# TB6600.net
KiCad netlist of a schematic drawn in EasyEDA Pro
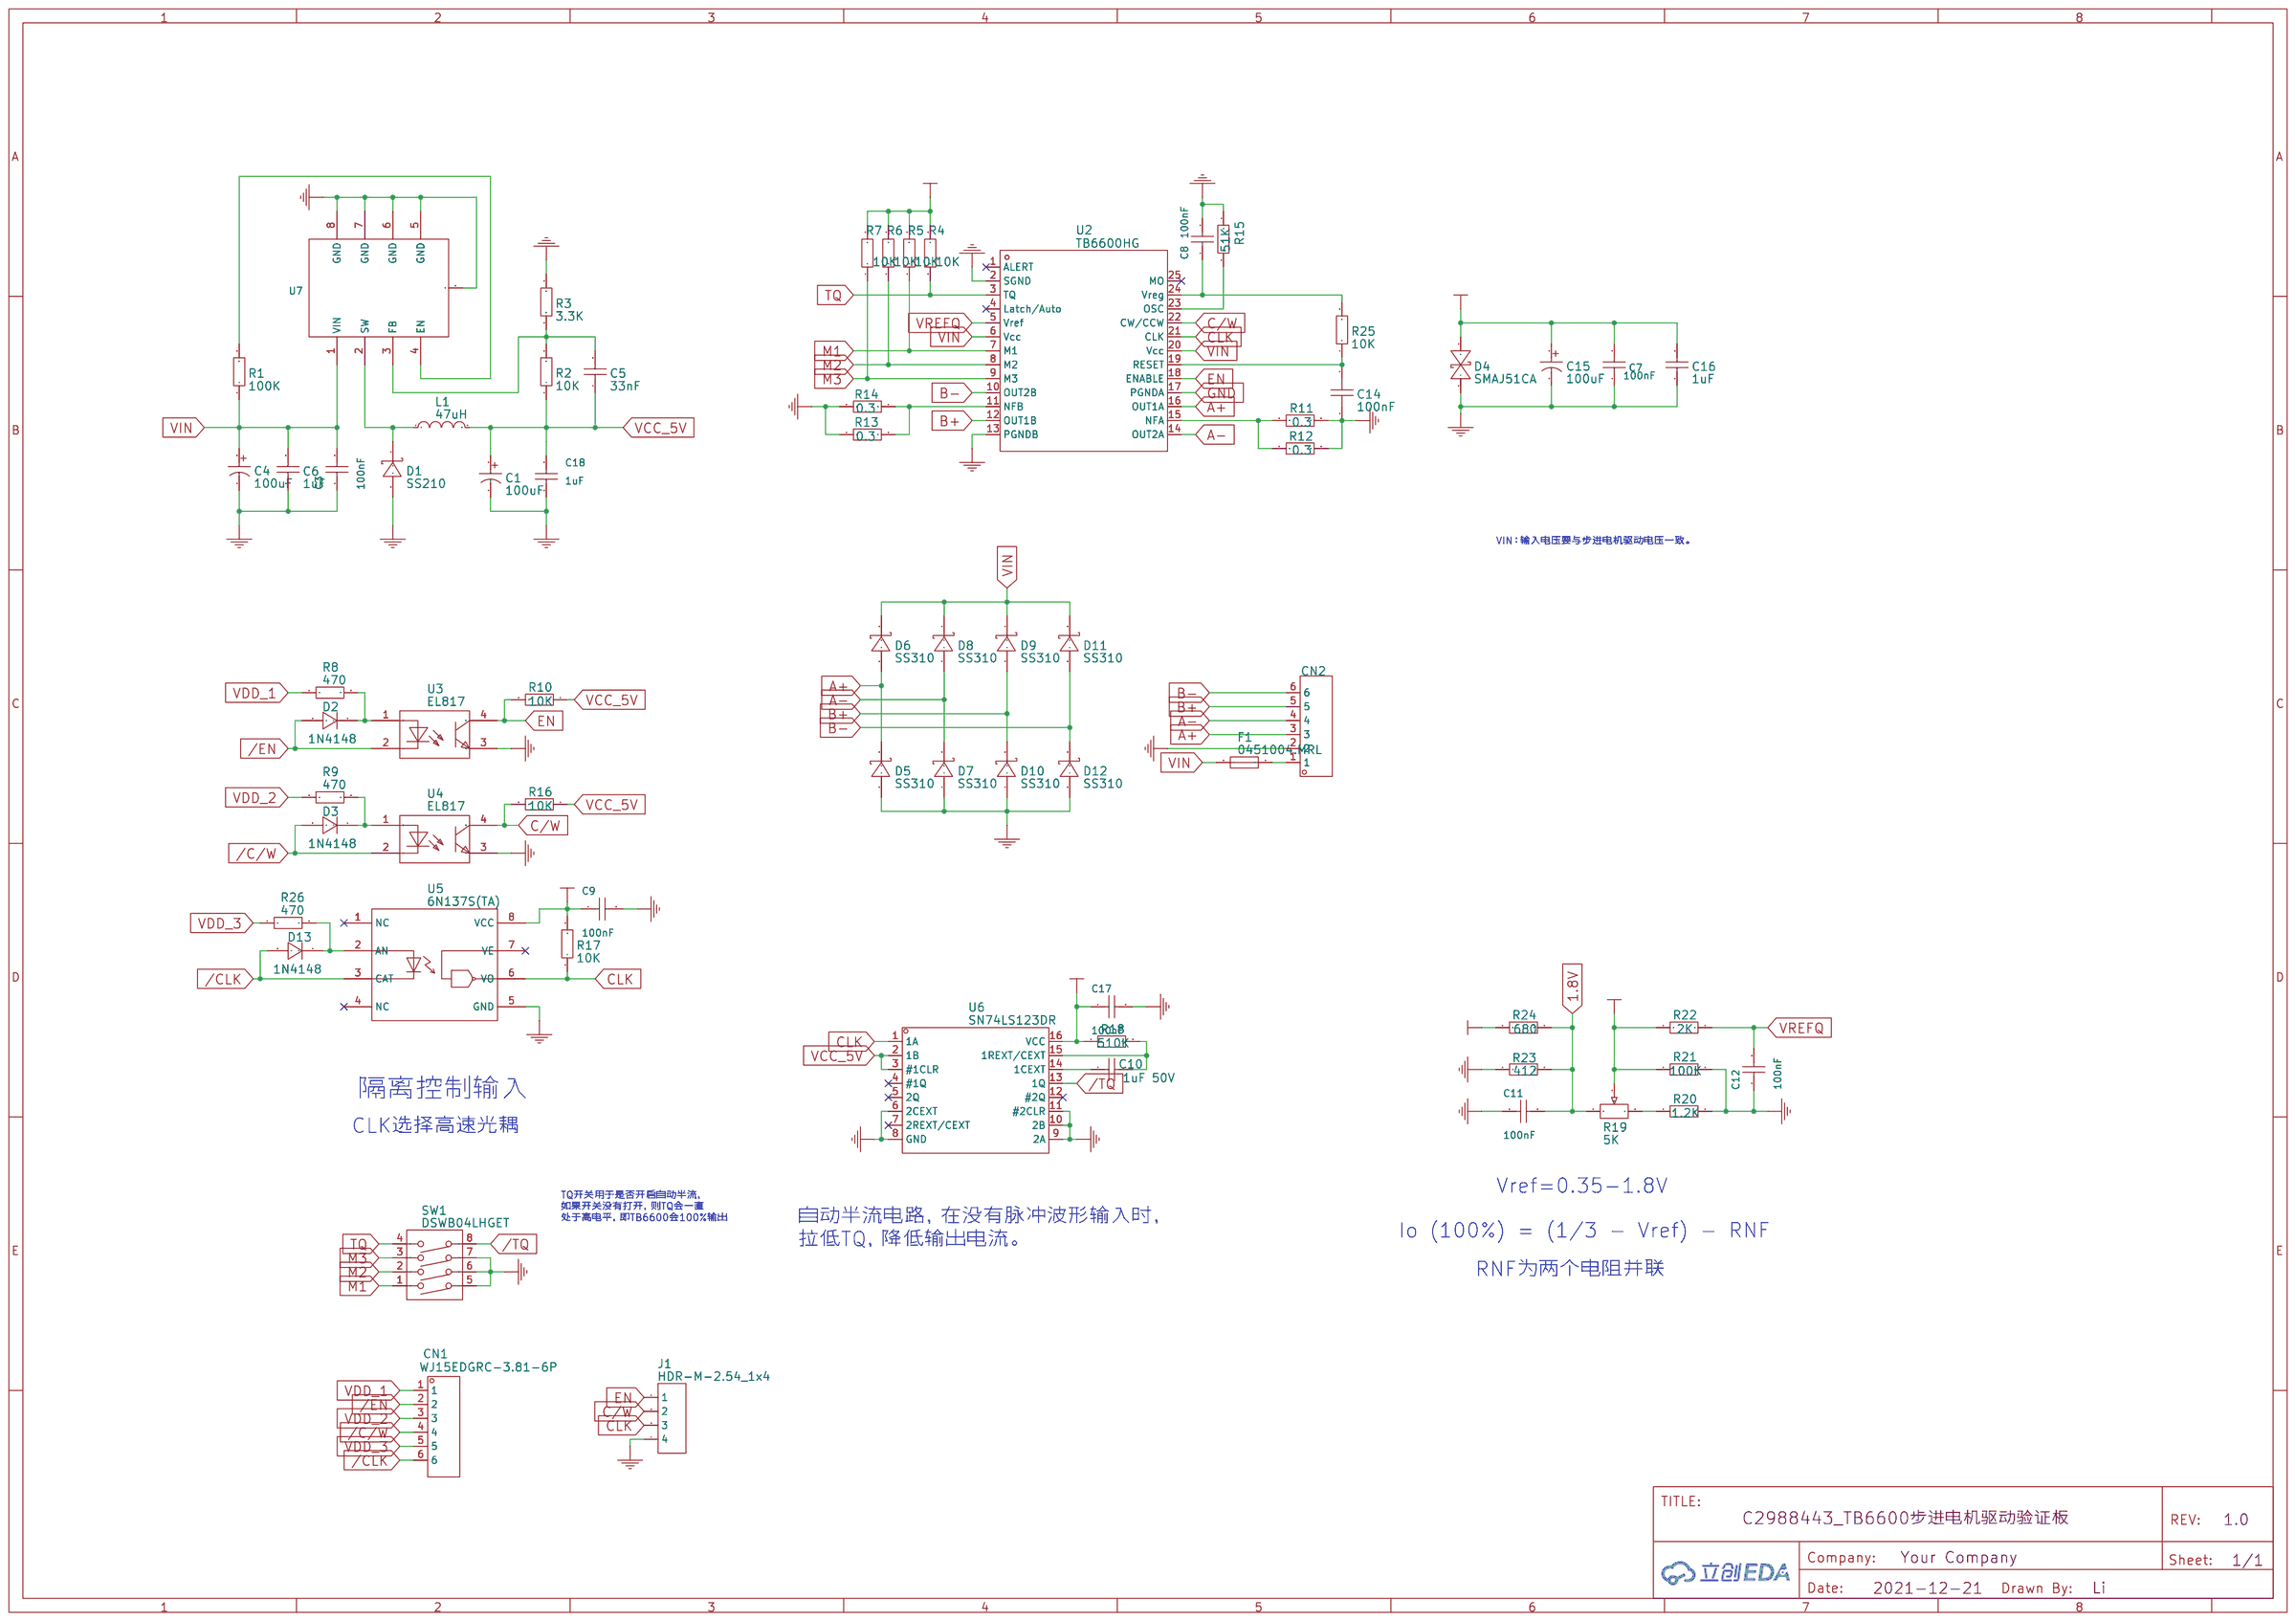
[diagram p0: schematic sheet]

(export (version "E")
  (design (tool "Eeschema 10.0.6"))
  (components
    (comp (ref "C1")
      (value "100uF")
      (footprint "easyedapro:CAP-TH_BD8.0-P3.50-D0.6-FD")
      (fields (field (name "Manufacturer Part") "50V 100uF 8X12") (field (name "Manufacturer") "ValuePro"))
      (libsource (lib "easyedapro") (part "100uF"))
    )
    (comp (ref "C3")
      (value "100nF")
      (footprint "easyedapro:C0603_1")
      (description "容值:100nF;精度:±10%;额定电压:50V;温度系数:X7R;")
      (fields (field (name "Manufacturer Part") "0603B104K500NT") (field (name "Manufacturer") "FH(风华)"))
      (libsource (lib "easyedapro") (part "0603B104K500NT"))
    )
    (comp (ref "C4")
      (value "100uF")
      (footprint "easyedapro:CAP-TH_BD8.0-P3.50-D0.6-FD")
      (fields (field (name "Manufacturer Part") "50V 100uF 8X12") (field (name "Manufacturer") "ValuePro"))
      (libsource (lib "easyedapro") (part "100uF"))
    )
    (comp (ref "C5")
      (value "33nF")
      (footprint "easyedapro:C0603")
      (fields
        (field (name "Manufacturer Part") "CL10B333JB8NNNC")
        (field (name "Manufacturer") "Samsung Electro-Mechanics")
      )
      (libsource (lib "easyedapro") (part "33nF"))
    )
    (comp (ref "C6")
      (value "1uF")
      (footprint "easyedapro:C0805")
      (fields (field (name "Manufacturer Part") "CL21B105KBFNNNE") (field (name "Manufacturer") "SAMSUNG"))
      (libsource (lib "easyedapro") (part "1uF"))
    )
    (comp (ref "C7")
      (value "100nF")
      (footprint "easyedapro:C0603_1")
      (description "容值:100nF;精度:±10%;额定电压:50V;温度系数:X7R;")
      (fields (field (name "Manufacturer Part") "0603B104K500NT") (field (name "Manufacturer") "FH(风华)"))
      (libsource (lib "easyedapro") (part "0603B104K500NT"))
    )
    (comp (ref "C8")
      (value "100nF")
      (footprint "easyedapro:C0603_1")
      (description "容值:100nF;精度:±10%;额定电压:50V;温度系数:X7R;")
      (fields (field (name "Manufacturer Part") "0603B104K500NT") (field (name "Manufacturer") "FH(风华)"))
      (libsource (lib "easyedapro") (part "0603B104K500NT"))
    )
    (comp (ref "C9")
      (value "100nF")
      (footprint "easyedapro:C0603_1")
      (description "容值:100nF;精度:±10%;额定电压:50V;温度系数:X7R;")
      (fields (field (name "Manufacturer Part") "0603B104K500NT") (field (name "Manufacturer") "FH(风华)"))
      (libsource (lib "easyedapro") (part "0603B104K500NT"))
    )
    (comp (ref "C10")
      (value "1uF 50V")
      (footprint "easyedapro:C0603")
      (fields (field (name "Manufacturer Part") "CL10A105KB8NNNC") (field (name "Manufacturer") "SAMSUNG"))
      (libsource (lib "easyedapro") (part "1uF 50V"))
    )
    (comp (ref "C11")
      (value "100nF")
      (footprint "easyedapro:C0603_1")
      (description "容值:100nF;精度:±10%;额定电压:50V;温度系数:X7R;")
      (fields (field (name "Manufacturer Part") "0603B104K500NT") (field (name "Manufacturer") "FH(风华)"))
      (libsource (lib "easyedapro") (part "0603B104K500NT"))
    )
    (comp (ref "C12")
      (value "100nF")
      (footprint "easyedapro:C0603_1")
      (description "容值:100nF;精度:±10%;额定电压:50V;温度系数:X7R;")
      (fields (field (name "Manufacturer Part") "0603B104K500NT") (field (name "Manufacturer") "FH(风华)"))
      (libsource (lib "easyedapro") (part "0603B104K500NT"))
    )
    (comp (ref "C14")
      (value "100nF")
      (footprint "easyedapro:C0603")
      (fields (field (name "Manufacturer Part") "0603B104K500NT") (field (name "Manufacturer") "FH"))
      (libsource (lib "easyedapro") (part "100nF"))
    )
    (comp (ref "C15")
      (value "100uF")
      (footprint "easyedapro:CAP-TH_BD8.0-P3.50-D0.6-FD")
      (fields (field (name "Manufacturer Part") "50V 100uF 8X12") (field (name "Manufacturer") "ValuePro"))
      (libsource (lib "easyedapro") (part "100uF"))
    )
    (comp (ref "C16")
      (value "1uF")
      (footprint "easyedapro:C0805")
      (fields (field (name "Manufacturer Part") "CL21B105KBFNNNE") (field (name "Manufacturer") "SAMSUNG"))
      (libsource (lib "easyedapro") (part "1uF"))
    )
    (comp (ref "C17")
      (value "100nF")
      (footprint "easyedapro:C0603_1")
      (description "容值:100nF;精度:±10%;额定电压:50V;温度系数:X7R;")
      (fields (field (name "Manufacturer Part") "0603B104K500NT") (field (name "Manufacturer") "FH(风华)"))
      (libsource (lib "easyedapro") (part "0603B104K500NT"))
    )
    (comp (ref "C18")
      (value "1uF")
      (footprint "easyedapro:C0603_1")
      (description "容值:1uF;精度:±10%;额定电压:50V;温度系数:X5R;")
      (fields
        (field (name "Manufacturer Part") "CL10A105KB8NNNC")
        (field (name "Manufacturer") "SAMSUNG(三星)")
      )
      (libsource (lib "easyedapro") (part "CL10A105KB8NNNC"))
    )
    (comp (ref "CN1")
      (value "WJ15EDGRC-3.81-6P")
      (footprint "easyedapro:CONN-TH_WJ15EDGRC-3.81-6P")
      (fields (field (name "Manufacturer") "ReliaPro"))
      (libsource (lib "easyedapro") (part "WJ15EDGRC-3.81-6P"))
    )
    (comp (ref "CN2")
      (value "WJ15EDGRC-3.81-6P")
      (footprint "easyedapro:CONN-TH_WJ15EDGRC-3.81-6P")
      (fields (field (name "Manufacturer") "ReliaPro"))
      (libsource (lib "easyedapro") (part "WJ15EDGRC-3.81-6P"))
    )
    (comp (ref "D1")
      (value "SS210")
      (footprint "easyedapro:SMA_L4.3-W2.6-LS5.2-RD")
      (fields (field (name "Manufacturer") "MDD"))
      (libsource (lib "easyedapro") (part "SS210"))
    )
    (comp (ref "D2")
      (value "1N4148")
      (footprint "easyedapro:SOD-123_L2.8-W1.8-LS3.7-RD")
      (fields (field (name "Manufacturer Part") "1N4148W T4") (field (name "Manufacturer") "CJ"))
      (libsource (lib "easyedapro") (part "1N4148"))
    )
    (comp (ref "D3")
      (value "1N4148")
      (footprint "easyedapro:SOD-123_L2.8-W1.8-LS3.7-RD")
      (fields (field (name "Manufacturer Part") "1N4148W T4") (field (name "Manufacturer") "CJ"))
      (libsource (lib "easyedapro") (part "1N4148"))
    )
    (comp (ref "D4")
      (value "SMAJ51CA")
      (footprint "easyedapro:SMA_L4.4-W2.6-LS5.0-BI")
      (fields (field (name "Manufacturer") "MDD（Microdiode Electronics）"))
      (libsource (lib "easyedapro") (part "SMAJ51CA"))
    )
    (comp (ref "D5")
      (value "SS310")
      (footprint "easyedapro:SMA_L4.3-W2.6-LS5.2-RD")
      (fields (field (name "Manufacturer") "MDD"))
      (libsource (lib "easyedapro") (part "SS310"))
    )
    (comp (ref "D6")
      (value "SS310")
      (footprint "easyedapro:SMA_L4.3-W2.6-LS5.2-RD")
      (fields (field (name "Manufacturer") "MDD"))
      (libsource (lib "easyedapro") (part "SS310"))
    )
    (comp (ref "D7")
      (value "SS310")
      (footprint "easyedapro:SMA_L4.3-W2.6-LS5.2-RD")
      (fields (field (name "Manufacturer") "MDD"))
      (libsource (lib "easyedapro") (part "SS310"))
    )
    (comp (ref "D8")
      (value "SS310")
      (footprint "easyedapro:SMA_L4.3-W2.6-LS5.2-RD")
      (fields (field (name "Manufacturer") "MDD"))
      (libsource (lib "easyedapro") (part "SS310"))
    )
    (comp (ref "D9")
      (value "SS310")
      (footprint "easyedapro:SMA_L4.3-W2.6-LS5.2-RD")
      (fields (field (name "Manufacturer") "MDD"))
      (libsource (lib "easyedapro") (part "SS310"))
    )
    (comp (ref "D10")
      (value "SS310")
      (footprint "easyedapro:SMA_L4.3-W2.6-LS5.2-RD")
      (fields (field (name "Manufacturer") "MDD"))
      (libsource (lib "easyedapro") (part "SS310"))
    )
    (comp (ref "D11")
      (value "SS310")
      (footprint "easyedapro:SMA_L4.3-W2.6-LS5.2-RD")
      (fields (field (name "Manufacturer") "MDD"))
      (libsource (lib "easyedapro") (part "SS310"))
    )
    (comp (ref "D12")
      (value "SS310")
      (footprint "easyedapro:SMA_L4.3-W2.6-LS5.2-RD")
      (fields (field (name "Manufacturer") "MDD"))
      (libsource (lib "easyedapro") (part "SS310"))
    )
    (comp (ref "D13")
      (value "1N4148")
      (footprint "easyedapro:SOD-123_L2.8-W1.8-LS3.7-RD")
      (fields (field (name "Manufacturer Part") "1N4148W T4") (field (name "Manufacturer") "CJ"))
      (libsource (lib "easyedapro") (part "1N4148"))
    )
    (comp (ref "F1")
      (value "0451004.MRL")
      (footprint "easyedapro:FUSE-SMD_L6.1-W2.7")
      (fields (field (name "Manufacturer") "Littelfuse"))
      (libsource (lib "easyedapro") (part "0451004.MRL"))
    )
    (comp (ref "J1")
      (value "HDR-M-2.54_1x4")
      (footprint "easyedapro:HDR-M-2.54_1X4")
      (libsource (lib "easyedapro") (part "HDR-M-2.54_1x4"))
    )
    (comp (ref "L1")
      (value "47uH")
      (footprint "easyedapro:IND-SMD_L4.0-W4.0_SMNR4018")
      (fields (field (name "Manufacturer Part") "SMNR4018-470MT") (field (name "Manufacturer") "SXN"))
      (libsource (lib "easyedapro") (part "47uH"))
    )
    (comp (ref "R1")
      (value "100K")
      (footprint "easyedapro:R0603")
      (fields (field (name "Manufacturer Part") "0603WAF1003T5E") (field (name "Manufacturer") "UniOhm"))
      (libsource (lib "easyedapro") (part "100K"))
    )
    (comp (ref "R2")
      (value "10K")
      (footprint "easyedapro:R0603")
      (fields (field (name "Manufacturer Part") "RC0603JR-0710KL") (field (name "Manufacturer") "YAGEO"))
      (libsource (lib "easyedapro") (part "10K"))
    )
    (comp (ref "R3")
      (value "3.3K")
      (footprint "easyedapro:R0603")
      (fields (field (name "Manufacturer Part") "0603WAF3301T5E") (field (name "Manufacturer") "UniOhm"))
      (libsource (lib "easyedapro") (part "3.3K"))
    )
    (comp (ref "R4")
      (value "10K")
      (footprint "easyedapro:R0603")
      (fields (field (name "Manufacturer Part") "RC0603JR-0710KL") (field (name "Manufacturer") "YAGEO"))
      (libsource (lib "easyedapro") (part "10K"))
    )
    (comp (ref "R5")
      (value "10K")
      (footprint "easyedapro:R0603")
      (fields (field (name "Manufacturer Part") "RC0603JR-0710KL") (field (name "Manufacturer") "YAGEO"))
      (libsource (lib "easyedapro") (part "10K"))
    )
    (comp (ref "R6")
      (value "10K")
      (footprint "easyedapro:R0603")
      (fields (field (name "Manufacturer Part") "RC0603JR-0710KL") (field (name "Manufacturer") "YAGEO"))
      (libsource (lib "easyedapro") (part "10K"))
    )
    (comp (ref "R7")
      (value "10K")
      (footprint "easyedapro:R0603")
      (fields (field (name "Manufacturer Part") "RC0603JR-0710KL") (field (name "Manufacturer") "YAGEO"))
      (libsource (lib "easyedapro") (part "10K"))
    )
    (comp (ref "R8")
      (value "470")
      (footprint "easyedapro:R0603")
      (fields (field (name "Manufacturer Part") "0603WAF4700T5E") (field (name "Manufacturer") "UniOhm"))
      (libsource (lib "easyedapro") (part "470"))
    )
    (comp (ref "R9")
      (value "470")
      (footprint "easyedapro:R0603")
      (fields (field (name "Manufacturer Part") "0603WAF4700T5E") (field (name "Manufacturer") "UniOhm"))
      (libsource (lib "easyedapro") (part "470"))
    )
    (comp (ref "R10")
      (value "10K")
      (footprint "easyedapro:R0603")
      (fields (field (name "Manufacturer Part") "RC0603JR-0710KL") (field (name "Manufacturer") "YAGEO"))
      (libsource (lib "easyedapro") (part "10K"))
    )
    (comp (ref "R11")
      (value "0.3")
      (footprint "easyedapro:R2512")
      (fields (field (name "Manufacturer Part") "25121WF300LT4F") (field (name "Manufacturer") "UniOhm"))
      (libsource (lib "easyedapro") (part "0.3"))
    )
    (comp (ref "R12")
      (value "0.3")
      (footprint "easyedapro:R2512")
      (fields (field (name "Manufacturer Part") "25121WF300LT4F") (field (name "Manufacturer") "UniOhm"))
      (libsource (lib "easyedapro") (part "0.3"))
    )
    (comp (ref "R13")
      (value "0.3")
      (footprint "easyedapro:R2512")
      (fields (field (name "Manufacturer Part") "25121WF300LT4F") (field (name "Manufacturer") "UniOhm"))
      (libsource (lib "easyedapro") (part "0.3"))
    )
    (comp (ref "R14")
      (value "0.3")
      (footprint "easyedapro:R2512")
      (fields (field (name "Manufacturer Part") "25121WF300LT4F") (field (name "Manufacturer") "UniOhm"))
      (libsource (lib "easyedapro") (part "0.3"))
    )
    (comp (ref "R15")
      (value "51K")
      (footprint "easyedapro:R0603")
      (fields (field (name "Manufacturer Part") "0603WAJ0513T5E") (field (name "Manufacturer") "UniOhm"))
      (libsource (lib "easyedapro") (part "51K"))
    )
    (comp (ref "R16")
      (value "10K")
      (footprint "easyedapro:R0603")
      (fields (field (name "Manufacturer Part") "RC0603JR-0710KL") (field (name "Manufacturer") "YAGEO"))
      (libsource (lib "easyedapro") (part "10K"))
    )
    (comp (ref "R17")
      (value "10K")
      (footprint "easyedapro:R0603")
      (fields (field (name "Manufacturer Part") "RC0603JR-0710KL") (field (name "Manufacturer") "YAGEO"))
      (libsource (lib "easyedapro") (part "10K"))
    )
    (comp (ref "R18")
      (value "510K")
      (footprint "easyedapro:R0603")
      (fields (field (name "Manufacturer Part") "0603WAF5103T5E") (field (name "Manufacturer") "UniOhm"))
      (libsource (lib "easyedapro") (part "510K"))
    )
    (comp (ref "R19")
      (value "5K")
      (footprint "easyedapro:RES-ADJ-TH_3P-L9.5-W9.5-P2.50-L_3386P")
      (fields
        (field (name "Manufacturer Part") "3386P-1-502")
        (field (name "Manufacturer") "Chengdu Guosheng Tech")
      )
      (libsource (lib "easyedapro") (part "5K"))
    )
    (comp (ref "R20")
      (value "1.2K")
      (footprint "easyedapro:R0603")
      (fields (field (name "Manufacturer Part") "0603WAF1201T5E") (field (name "Manufacturer") "UniOhm"))
      (libsource (lib "easyedapro") (part "1.2K"))
    )
    (comp (ref "R21")
      (value "100K")
      (footprint "easyedapro:R0603")
      (fields (field (name "Manufacturer Part") "0603WAF1003T5E") (field (name "Manufacturer") "UniOhm"))
      (libsource (lib "easyedapro") (part "100K"))
    )
    (comp (ref "R22")
      (value "2K")
      (footprint "easyedapro:R0603")
      (fields (field (name "Manufacturer Part") "0603WAF2001T5E") (field (name "Manufacturer") "UniOhm"))
      (libsource (lib "easyedapro") (part "2K"))
    )
    (comp (ref "R23")
      (value "412")
      (footprint "easyedapro:R0603")
      (fields (field (name "Manufacturer Part") "0603WAF4120T5E") (field (name "Manufacturer") "UniOhm"))
      (libsource (lib "easyedapro") (part "412"))
    )
    (comp (ref "R24")
      (value "680")
      (footprint "easyedapro:R0603")
      (fields (field (name "Manufacturer Part") "0603WAF6800T5E") (field (name "Manufacturer") "UniOhm"))
      (libsource (lib "easyedapro") (part "680"))
    )
    (comp (ref "R25")
      (value "10K")
      (footprint "easyedapro:R0603")
      (fields (field (name "Manufacturer Part") "RC0603JR-0710KL") (field (name "Manufacturer") "YAGEO"))
      (libsource (lib "easyedapro") (part "10K"))
    )
    (comp (ref "R26")
      (value "470")
      (footprint "easyedapro:R0603")
      (fields (field (name "Manufacturer Part") "0603WAF4700T5E") (field (name "Manufacturer") "UniOhm"))
      (libsource (lib "easyedapro") (part "470"))
    )
    (comp (ref "SW1")
      (value "DSWB04LHGET")
      (footprint "easyedapro:SW-TH_DSWB04LHGET")
      (fields (field (name "Manufacturer") "Dongguan Guangzhu Industrial"))
      (libsource (lib "easyedapro") (part "DSWB04LHGET"))
    )
    (comp (ref "U2")
      (value "TB6600HG")
      (footprint "easyedapro:HZIP25-P-1.0_TB6600HG")
      (fields (field (name "Manufacturer") "TOSHIBA"))
      (libsource (lib "easyedapro") (part "TB6600HG"))
    )
    (comp (ref "U3")
      (value "EL817")
      (footprint "easyedapro:OPTO-SMD-4_L4.6-W6.5-P2.54-LS10.3-TL")
      (fields (field (name "Manufacturer Part") "EL817S1(C)(TU)-F") (field (name "Manufacturer") "EVERLIGHT"))
      (libsource (lib "easyedapro") (part "EL817"))
    )
    (comp (ref "U4")
      (value "EL817")
      (footprint "easyedapro:OPTO-SMD-4_L4.6-W6.5-P2.54-LS10.3-TL")
      (fields (field (name "Manufacturer Part") "EL817S1(C)(TU)-F") (field (name "Manufacturer") "EVERLIGHT"))
      (libsource (lib "easyedapro") (part "EL817"))
    )
    (comp (ref "U5")
      (value "6N137S(TA)")
      (footprint "easyedapro:SMD-8_L9.8-W6.6-P2.54-LS10.3-BL")
      (fields (field (name "Manufacturer") "EVERLIGHT"))
      (libsource (lib "easyedapro") (part "6N137S(TA)"))
    )
    (comp (ref "U6")
      (value "SN74LS123DR")
      (footprint "easyedapro:SOIC-16_L9.9-W3.9-P1.27-LS6.0-BL")
      (fields (field (name "Manufacturer") "Texas Instruments"))
      (libsource (lib "easyedapro") (part "SN74LS123DR"))
    )
    (comp (ref "U7")
      (value "~")
      (footprint "easyedapro:SOIC-8_L5.0-W4.0-P1.27-LS6.0-BL-EP2.0_1")
      (description "功能类型:降压型;同步整流:-;输出通道数:-;拓扑结构:-;输入电压:-;输出电流(最大值):-;开关频率:-;")
      (fields (field (name "Manufacturer Part") "XL7005A") (field (name "Manufacturer") "XLSEMI(芯龙)"))
      (libsource (lib "easyedapro") (part "XL7005A_1"))
    )
  )
  (nets
    (net (code "1") (name "1.8V") (class "Default")
      (node (ref "C11") (pin "2") (pinfunction "2_2") (pintype "input"))
      (node (ref "R19") (pin "1") (pinfunction "1_1") (pintype "input"))
      (node (ref "R23") (pin "1") (pinfunction "1_1") (pintype "input"))
      (node (ref "R24") (pin "1") (pinfunction "1_1") (pintype "input"))
    )
    (net (code "2") (name "A+") (class "Default")
      (node (ref "CN2") (pin "3") (pinfunction "3_3") (pintype "input"))
      (node (ref "D5") (pin "1") (pinfunction "K_1") (pintype "input"))
      (node (ref "D6") (pin "2") (pinfunction "A_2") (pintype "input"))
      (node (ref "U2") (pin "16") (pinfunction "OUT1A_16") (pintype "input"))
    )
    (net (code "3") (name "A-") (class "Default")
      (node (ref "CN2") (pin "4") (pinfunction "4_4") (pintype "input"))
      (node (ref "D7") (pin "1") (pinfunction "K_1") (pintype "input"))
      (node (ref "D8") (pin "2") (pinfunction "A_2") (pintype "input"))
      (node (ref "U2") (pin "14") (pinfunction "OUT2A_14") (pintype "input"))
    )
    (net (code "4") (name "B+") (class "Default")
      (node (ref "CN2") (pin "5") (pinfunction "5_5") (pintype "input"))
      (node (ref "D10") (pin "1") (pinfunction "K_1") (pintype "input"))
      (node (ref "D9") (pin "2") (pinfunction "A_2") (pintype "input"))
      (node (ref "U2") (pin "12") (pinfunction "OUT1B_12") (pintype "input"))
    )
    (net (code "5") (name "B-") (class "Default")
      (node (ref "CN2") (pin "6") (pinfunction "6_6") (pintype "input"))
      (node (ref "D11") (pin "2") (pinfunction "A_2") (pintype "input"))
      (node (ref "D12") (pin "1") (pinfunction "K_1") (pintype "input"))
      (node (ref "U2") (pin "10") (pinfunction "OUT2B_10") (pintype "input"))
    )
    (net (code "6") (name "CLK") (class "Default")
      (node (ref "J1") (pin "3") (pinfunction "3_3") (pintype "input"))
      (node (ref "R17") (pin "1") (pinfunction "1_1") (pintype "input"))
      (node (ref "U2") (pin "21") (pinfunction "CLK_21") (pintype "input"))
      (node (ref "U5") (pin "6") (pinfunction "VO_6") (pintype "input"))
      (node (ref "U6") (pin "1") (pinfunction "1A_1") (pintype "input"))
    )
    (net (code "7") (name "C{slash}W") (class "Default")
      (node (ref "J1") (pin "2") (pinfunction "2_2") (pintype "input"))
      (node (ref "R16") (pin "2") (pinfunction "2_2") (pintype "input"))
      (node (ref "U2") (pin "22") (pinfunction "CW/CCW_22") (pintype "input"))
      (node (ref "U4") (pin "4") (pinfunction "COL_4") (pintype "input"))
    )
    (net (code "8") (name "EN") (class "Default")
      (node (ref "J1") (pin "1") (pinfunction "1_1") (pintype "input"))
      (node (ref "R10") (pin "2") (pinfunction "2_2") (pintype "input"))
      (node (ref "U2") (pin "18") (pinfunction "ENABLE_18") (pintype "input"))
      (node (ref "U3") (pin "4") (pinfunction "COL_4") (pintype "input"))
    )
    (net (code "9") (name "GND") (class "Default")
      (node (ref "C1") (pin "2") (pinfunction "2_2") (pintype "input"))
      (node (ref "C11") (pin "1") (pinfunction "1_1") (pintype "input"))
      (node (ref "C12") (pin "1") (pinfunction "1_1") (pintype "input"))
      (node (ref "C14") (pin "1") (pinfunction "1_1") (pintype "input"))
      (node (ref "C15") (pin "2") (pinfunction "2_2") (pintype "input"))
      (node (ref "C16") (pin "1") (pinfunction "1_1") (pintype "input"))
      (node (ref "C17") (pin "2") (pinfunction "2_2") (pintype "input"))
      (node (ref "C18") (pin "1") (pinfunction "1_1") (pintype "input"))
      (node (ref "C3") (pin "1") (pinfunction "1_1") (pintype "input"))
      (node (ref "C4") (pin "2") (pinfunction "2_2") (pintype "input"))
      (node (ref "C6") (pin "1") (pinfunction "1_1") (pintype "input"))
      (node (ref "C7") (pin "1") (pinfunction "1_1") (pintype "input"))
      (node (ref "C8") (pin "2") (pinfunction "2_2") (pintype "input"))
      (node (ref "C9") (pin "2") (pinfunction "2_2") (pintype "input"))
      (node (ref "CN2") (pin "2") (pinfunction "2_2") (pintype "input"))
      (node (ref "D1") (pin "2") (pinfunction "A_2") (pintype "input"))
      (node (ref "D10") (pin "2") (pinfunction "A_2") (pintype "input"))
      (node (ref "D12") (pin "2") (pinfunction "A_2") (pintype "input"))
      (node (ref "D4") (pin "1") (pinfunction "A_1") (pintype "input"))
      (node (ref "D5") (pin "2") (pinfunction "A_2") (pintype "input"))
      (node (ref "D7") (pin "2") (pinfunction "A_2") (pintype "input"))
      (node (ref "J1") (pin "4") (pinfunction "4_4") (pintype "input"))
      (node (ref "R11") (pin "2") (pinfunction "2_2") (pintype "input"))
      (node (ref "R12") (pin "2") (pinfunction "2_2") (pintype "input"))
      (node (ref "R13") (pin "1") (pinfunction "1_1") (pintype "input"))
      (node (ref "R14") (pin "1") (pinfunction "1_1") (pintype "input"))
      (node (ref "R15") (pin "2") (pinfunction "2_2") (pintype "input"))
      (node (ref "R20") (pin "2") (pinfunction "2_2") (pintype "input"))
      (node (ref "R21") (pin "2") (pinfunction "2_2") (pintype "input"))
      (node (ref "R23") (pin "2") (pinfunction "2_2") (pintype "input"))
      (node (ref "R3") (pin "2") (pinfunction "2_2") (pintype "input"))
      (node (ref "SW1") (pin "5") (pinfunction "5_5") (pintype "input"))
      (node (ref "SW1") (pin "6") (pinfunction "6_6") (pintype "input"))
      (node (ref "SW1") (pin "7") (pinfunction "7_7") (pintype "input"))
      (node (ref "U2") (pin "13") (pinfunction "PGNDB_13") (pintype "input"))
      (node (ref "U2") (pin "17") (pinfunction "PGNDA_17") (pintype "input"))
      (node (ref "U2") (pin "2") (pinfunction "SGND_2") (pintype "input"))
      (node (ref "U3") (pin "3") (pinfunction "EM_3") (pintype "input"))
      (node (ref "U4") (pin "3") (pinfunction "EM_3") (pintype "input"))
      (node (ref "U5") (pin "5") (pinfunction "GND_5") (pintype "input"))
      (node (ref "U6") (pin "10") (pinfunction "2B_10") (pintype "input"))
      (node (ref "U6") (pin "11") (pinfunction "#2CLR_11") (pintype "input"))
      (node (ref "U6") (pin "6") (pinfunction "2CEXT_6") (pintype "input"))
      (node (ref "U6") (pin "8") (pinfunction "GND_8") (pintype "input"))
      (node (ref "U6") (pin "9") (pinfunction "2A_9") (pintype "input"))
      (node (ref "U7") (pin "5") (pinfunction "GND_5") (pintype "input"))
      (node (ref "U7") (pin "6") (pinfunction "GND_6") (pintype "input"))
      (node (ref "U7") (pin "7") (pinfunction "GND_7") (pintype "input"))
      (node (ref "U7") (pin "8") (pinfunction "GND_8") (pintype "input"))
      (node (ref "U7") (pin "9") (pinfunction "9_9") (pintype "input"))
    )
    (net (code "10") (name "M1") (class "Default")
      (node (ref "R5") (pin "1") (pinfunction "1_1") (pintype "input"))
      (node (ref "SW1") (pin "1") (pinfunction "1_1") (pintype "input"))
      (node (ref "U2") (pin "7") (pinfunction "M1_7") (pintype "input"))
    )
    (net (code "11") (name "M2") (class "Default")
      (node (ref "R6") (pin "1") (pinfunction "1_1") (pintype "input"))
      (node (ref "SW1") (pin "2") (pinfunction "2_2") (pintype "input"))
      (node (ref "U2") (pin "8") (pinfunction "M2_8") (pintype "input"))
    )
    (net (code "12") (name "M3") (class "Default")
      (node (ref "R7") (pin "1") (pinfunction "1_1") (pintype "input"))
      (node (ref "SW1") (pin "3") (pinfunction "3_3") (pintype "input"))
      (node (ref "U2") (pin "9") (pinfunction "M3_9") (pintype "input"))
    )
    (net (code "13") (name "Net-(CN2-Pad1)") (class "Default")
      (node (ref "CN2") (pin "1") (pinfunction "1_1") (pintype "input"))
      (node (ref "F1") (pin "2") (pinfunction "2_2") (pintype "input"))
    )
    (net (code "14") (name "Net-(D1-K)") (class "Default")
      (node (ref "D1") (pin "1") (pinfunction "K_1") (pintype "input"))
      (node (ref "L1") (pin "1") (pinfunction "1_1") (pintype "input"))
      (node (ref "U7") (pin "2") (pinfunction "SW_2") (pintype "input"))
    )
    (net (code "15") (name "Net-(D2-K)") (class "Default")
      (node (ref "D2") (pin "1") (pinfunction "K_1") (pintype "input"))
      (node (ref "R8") (pin "2") (pinfunction "2_2") (pintype "input"))
      (node (ref "U3") (pin "1") (pinfunction "AN_1") (pintype "input"))
    )
    (net (code "16") (name "Net-(D3-K)") (class "Default")
      (node (ref "D3") (pin "1") (pinfunction "K_1") (pintype "input"))
      (node (ref "R9") (pin "2") (pinfunction "2_2") (pintype "input"))
      (node (ref "U4") (pin "1") (pinfunction "AN_1") (pintype "input"))
    )
    (net (code "17") (name "Net-(D13-K)") (class "Default")
      (node (ref "D13") (pin "1") (pinfunction "K_1") (pintype "input"))
      (node (ref "R26") (pin "2") (pinfunction "2_2") (pintype "input"))
      (node (ref "U5") (pin "2") (pinfunction "AN_2") (pintype "input"))
    )
    (net (code "18") (name "Net-(R19-Pad3)") (class "Default")
      (node (ref "R19") (pin "3") (pinfunction "3_3") (pintype "input"))
      (node (ref "R20") (pin "1") (pinfunction "1_1") (pintype "input"))
    )
    (net (code "19") (name "Net-(U2-NFA)") (class "Default")
      (node (ref "R11") (pin "1") (pinfunction "1_1") (pintype "input"))
      (node (ref "R12") (pin "1") (pinfunction "1_1") (pintype "input"))
      (node (ref "U2") (pin "15") (pinfunction "NFA_15") (pintype "input"))
    )
    (net (code "20") (name "Net-(U2-NFB)") (class "Default")
      (node (ref "R13") (pin "2") (pinfunction "2_2") (pintype "input"))
      (node (ref "R14") (pin "2") (pinfunction "2_2") (pintype "input"))
      (node (ref "U2") (pin "11") (pinfunction "NFB_11") (pintype "input"))
    )
    (net (code "21") (name "Net-(U2-OSC)") (class "Default")
      (node (ref "R15") (pin "1") (pinfunction "1_1") (pintype "input"))
      (node (ref "U2") (pin "23") (pinfunction "OSC_23") (pintype "input"))
    )
    (net (code "22") (name "Net-(U2-RESET)") (class "Default")
      (node (ref "C14") (pin "2") (pinfunction "2_2") (pintype "input"))
      (node (ref "R25") (pin "1") (pinfunction "1_1") (pintype "input"))
      (node (ref "U2") (pin "19") (pinfunction "RESET_19") (pintype "input"))
    )
    (net (code "23") (name "Net-(U2-Vreg)") (class "Default")
      (node (ref "C8") (pin "1") (pinfunction "1_1") (pintype "input"))
      (node (ref "R25") (pin "2") (pinfunction "2_2") (pintype "input"))
      (node (ref "U2") (pin "24") (pinfunction "Vreg_24") (pintype "input"))
    )
    (net (code "24") (name "Net-(U6-1CEXT)") (class "Default")
      (node (ref "C10") (pin "2") (pinfunction "2_2") (pintype "input"))
      (node (ref "U6") (pin "14") (pinfunction "1CEXT_14") (pintype "input"))
    )
    (net (code "25") (name "Net-(U6-1REXT{slash}CEXT)") (class "Default")
      (node (ref "C10") (pin "1") (pinfunction "1_1") (pintype "input"))
      (node (ref "R18") (pin "2") (pinfunction "2_2") (pintype "input"))
      (node (ref "U6") (pin "15") (pinfunction "1REXT/CEXT_15") (pintype "input"))
    )
    (net (code "26") (name "Net-(U7-EN)") (class "Default")
      (node (ref "R1") (pin "2") (pinfunction "2_2") (pintype "input"))
      (node (ref "U7") (pin "4") (pinfunction "EN_4") (pintype "input"))
    )
    (net (code "27") (name "Net-(U7-FB)") (class "Default")
      (node (ref "C5") (pin "2") (pinfunction "2_2") (pintype "input"))
      (node (ref "R2") (pin "2") (pinfunction "2_2") (pintype "input"))
      (node (ref "R3") (pin "1") (pinfunction "1_1") (pintype "input"))
      (node (ref "U7") (pin "3") (pinfunction "FB_3") (pintype "input"))
    )
    (net (code "28") (name "TQ") (class "Default")
      (node (ref "R4") (pin "1") (pinfunction "1_1") (pintype "input"))
      (node (ref "SW1") (pin "4") (pinfunction "4_4") (pintype "input"))
      (node (ref "U2") (pin "3") (pinfunction "TQ_3") (pintype "input"))
    )
    (net (code "29") (name "VCC_5V") (class "Default")
      (node (ref "C1") (pin "1") (pinfunction "1_1") (pintype "input"))
      (node (ref "C17") (pin "1") (pinfunction "1_1") (pintype "input"))
      (node (ref "C18") (pin "2") (pinfunction "2_2") (pintype "input"))
      (node (ref "C5") (pin "1") (pinfunction "1_1") (pintype "input"))
      (node (ref "C9") (pin "1") (pinfunction "1_1") (pintype "input"))
      (node (ref "L1") (pin "2") (pinfunction "2_2") (pintype "input"))
      (node (ref "R10") (pin "1") (pinfunction "1_1") (pintype "input"))
      (node (ref "R16") (pin "1") (pinfunction "1_1") (pintype "input"))
      (node (ref "R17") (pin "2") (pinfunction "2_2") (pintype "input"))
      (node (ref "R18") (pin "1") (pinfunction "1_1") (pintype "input"))
      (node (ref "R2") (pin "1") (pinfunction "1_1") (pintype "input"))
      (node (ref "R24") (pin "2") (pinfunction "2_2") (pintype "input"))
      (node (ref "R4") (pin "2") (pinfunction "2_2") (pintype "input"))
      (node (ref "R5") (pin "2") (pinfunction "2_2") (pintype "input"))
      (node (ref "R6") (pin "2") (pinfunction "2_2") (pintype "input"))
      (node (ref "R7") (pin "2") (pinfunction "2_2") (pintype "input"))
      (node (ref "U5") (pin "8") (pinfunction "VCC_8") (pintype "input"))
      (node (ref "U6") (pin "16") (pinfunction "VCC_16") (pintype "input"))
      (node (ref "U6") (pin "2") (pinfunction "1B_2") (pintype "input"))
      (node (ref "U6") (pin "3") (pinfunction "#1CLR_3") (pintype "input"))
    )
    (net (code "30") (name "VDD_1") (class "Default")
      (node (ref "CN1") (pin "1") (pinfunction "1_1") (pintype "input"))
      (node (ref "R8") (pin "1") (pinfunction "1_1") (pintype "input"))
    )
    (net (code "31") (name "VDD_2") (class "Default")
      (node (ref "CN1") (pin "3") (pinfunction "3_3") (pintype "input"))
      (node (ref "R9") (pin "1") (pinfunction "1_1") (pintype "input"))
    )
    (net (code "32") (name "VDD_3") (class "Default")
      (node (ref "CN1") (pin "5") (pinfunction "5_5") (pintype "input"))
      (node (ref "R26") (pin "1") (pinfunction "1_1") (pintype "input"))
    )
    (net (code "33") (name "VIN") (class "Default")
      (node (ref "C15") (pin "1") (pinfunction "1_1") (pintype "input"))
      (node (ref "C16") (pin "2") (pinfunction "2_2") (pintype "input"))
      (node (ref "C3") (pin "2") (pinfunction "2_2") (pintype "input"))
      (node (ref "C4") (pin "1") (pinfunction "1_1") (pintype "input"))
      (node (ref "C6") (pin "2") (pinfunction "2_2") (pintype "input"))
      (node (ref "C7") (pin "2") (pinfunction "2_2") (pintype "input"))
      (node (ref "D11") (pin "1") (pinfunction "K_1") (pintype "input"))
      (node (ref "D4") (pin "2") (pinfunction "K_2") (pintype "input"))
      (node (ref "D6") (pin "1") (pinfunction "K_1") (pintype "input"))
      (node (ref "D8") (pin "1") (pinfunction "K_1") (pintype "input"))
      (node (ref "D9") (pin "1") (pinfunction "K_1") (pintype "input"))
      (node (ref "F1") (pin "1") (pinfunction "1_1") (pintype "input"))
      (node (ref "R1") (pin "1") (pinfunction "1_1") (pintype "input"))
      (node (ref "U2") (pin "20") (pinfunction "Vcc_20") (pintype "input"))
      (node (ref "U2") (pin "6") (pinfunction "Vcc_6") (pintype "input"))
      (node (ref "U7") (pin "1") (pinfunction "VIN_1") (pintype "input"))
    )
    (net (code "34") (name "VREF") (class "Default")
      (node (ref "R19") (pin "2") (pinfunction "2_2") (pintype "input"))
      (node (ref "R21") (pin "1") (pinfunction "1_1") (pintype "input"))
      (node (ref "R22") (pin "1") (pinfunction "1_1") (pintype "input"))
    )
    (net (code "35") (name "VREFQ") (class "Default")
      (node (ref "C12") (pin "2") (pinfunction "2_2") (pintype "input"))
      (node (ref "R22") (pin "2") (pinfunction "2_2") (pintype "input"))
      (node (ref "U2") (pin "5") (pinfunction "Vref_5") (pintype "input"))
    )
    (net (code "36") (name "unconnected-(U2-ALERT-Pad1)") (class "Default")
      (node (ref "U2") (pin "1") (pinfunction "ALERT_1") (pintype "input+no_connect"))
    )
    (net (code "37") (name "unconnected-(U2-Latch{slash}Auto-Pad4)") (class "Default")
      (node (ref "U2") (pin "4") (pinfunction "Latch/Auto_4") (pintype "input+no_connect"))
    )
    (net (code "38") (name "unconnected-(U2-MO-Pad25)") (class "Default")
      (node (ref "U2") (pin "25") (pinfunction "MO_25") (pintype "input+no_connect"))
    )
    (net (code "39") (name "unconnected-(U5-NC-Pad1)") (class "Default")
      (node (ref "U5") (pin "1") (pinfunction "NC_1") (pintype "input+no_connect"))
    )
    (net (code "40") (name "unconnected-(U5-NC-Pad4)") (class "Default")
      (node (ref "U5") (pin "4") (pinfunction "NC_4") (pintype "input+no_connect"))
    )
    (net (code "41") (name "unconnected-(U5-VE-Pad7)") (class "Default")
      (node (ref "U5") (pin "7") (pinfunction "VE_7") (pintype "input+no_connect"))
    )
    (net (code "42") (name "unconnected-(U6-#1Q-Pad4)") (class "Default")
      (node (ref "U6") (pin "4") (pinfunction "#1Q_4") (pintype "input+no_connect"))
    )
    (net (code "43") (name "unconnected-(U6-#2Q-Pad12)") (class "Default")
      (node (ref "U6") (pin "12") (pinfunction "#2Q_12") (pintype "input+no_connect"))
    )
    (net (code "44") (name "unconnected-(U6-2Q-Pad5)") (class "Default")
      (node (ref "U6") (pin "5") (pinfunction "2Q_5") (pintype "input+no_connect"))
    )
    (net (code "45") (name "unconnected-(U6-2REXT{slash}CEXT-Pad7)") (class "Default")
      (node (ref "U6") (pin "7") (pinfunction "2REXT/CEXT_7") (pintype "input+no_connect"))
    )
    (net (code "46") (name "{slash}CLK") (class "Default")
      (node (ref "CN1") (pin "6") (pinfunction "6_6") (pintype "input"))
      (node (ref "D13") (pin "2") (pinfunction "A_2") (pintype "input"))
      (node (ref "U5") (pin "3") (pinfunction "CAT_3") (pintype "input"))
    )
    (net (code "47") (name "{slash}C{slash}W") (class "Default")
      (node (ref "CN1") (pin "4") (pinfunction "4_4") (pintype "input"))
      (node (ref "D3") (pin "2") (pinfunction "A_2") (pintype "input"))
      (node (ref "U4") (pin "2") (pinfunction "CAT_2") (pintype "input"))
    )
    (net (code "48") (name "{slash}EN") (class "Default")
      (node (ref "CN1") (pin "2") (pinfunction "2_2") (pintype "input"))
      (node (ref "D2") (pin "2") (pinfunction "A_2") (pintype "input"))
      (node (ref "U3") (pin "2") (pinfunction "CAT_2") (pintype "input"))
    )
    (net (code "49") (name "{slash}TQ") (class "Default")
      (node (ref "SW1") (pin "8") (pinfunction "8_8") (pintype "input"))
      (node (ref "U6") (pin "13") (pinfunction "1Q_13") (pintype "input"))
    )
  )
)
